# usb.net
KiCad netlist of a schematic drawn in EAGLE
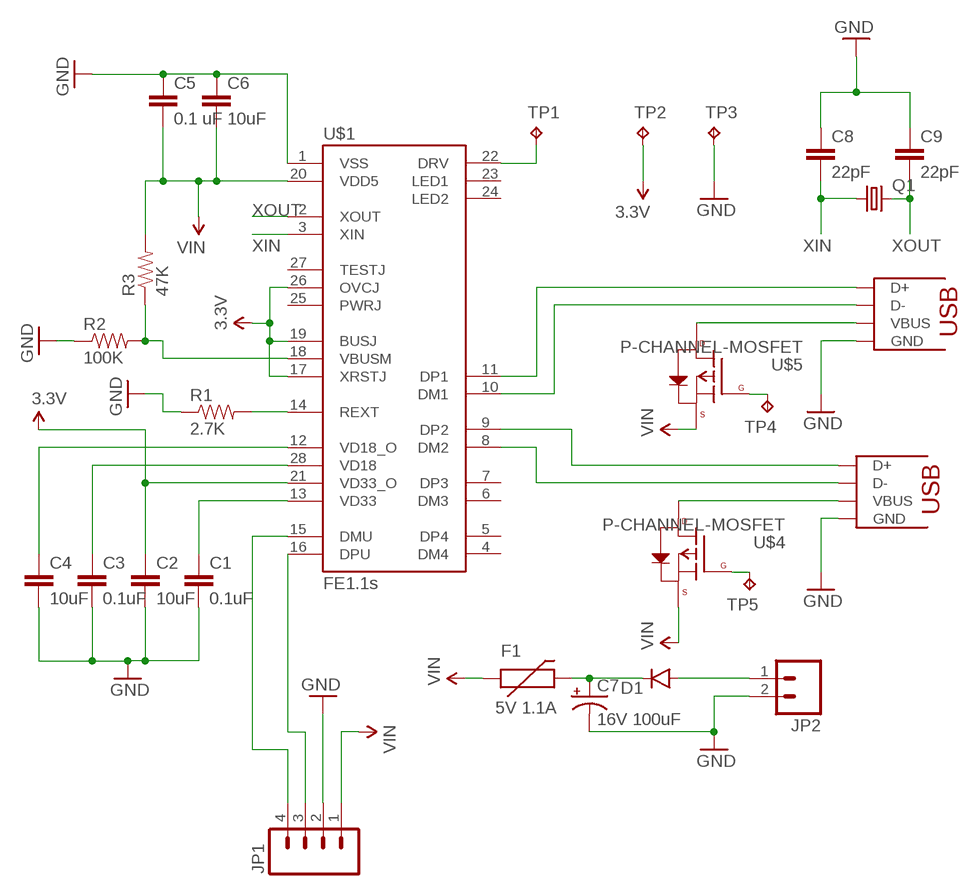
[diagram p0: schematic, sheet 1]

(export (version "E")
  (design (tool "Eeschema 10.0.6"))
  (components
    (comp (ref "C1")
      (value "0.1uF")
      (footprint "eagle-import:1206")
      (fields (field (name "MF") "TDK") (field (name "MPN") "CGA5L2C0G1H104J160AA"))
      (libsource (lib "eagle-import") (part "CAP1206"))
    )
    (comp (ref "C2")
      (value "10uF")
      (footprint "eagle-import:1206")
      (fields (field (name "MF") "TAIYO YUDEN") (field (name "MPN") "GMK316F106ZL-T"))
      (libsource (lib "eagle-import") (part "CAP1206"))
    )
    (comp (ref "C3")
      (value "0.1uF")
      (footprint "eagle-import:1206")
      (fields (field (name "MF") "TDK") (field (name "MPN") "CGA5L2C0G1H104J160AA"))
      (libsource (lib "eagle-import") (part "CAP1206"))
    )
    (comp (ref "C4")
      (value "10uF")
      (footprint "eagle-import:1206")
      (fields (field (name "MF") "TAIYO YUDEN") (field (name "MPN") "GMK316F106ZL-T"))
      (libsource (lib "eagle-import") (part "CAP1206"))
    )
    (comp (ref "C5")
      (value "0.1 uF")
      (footprint "eagle-import:1206")
      (fields (field (name "MF") "TDK") (field (name "MPN") "CGA5L2C0G1H104J160AA"))
      (libsource (lib "eagle-import") (part "CAP1206"))
    )
    (comp (ref "C6")
      (value "10uF")
      (footprint "eagle-import:1206")
      (fields (field (name "MF") "TAIYO YUDEN") (field (name "MPN") "GMK316F106ZL-T"))
      (libsource (lib "eagle-import") (part "CAP1206"))
    )
    (comp (ref "C7")
      (value "16V 100uF")
      (footprint "eagle-import:PANASONIC_D")
      (fields (field (name "MF") "PANASONIC ELECTRONIC COMPONENTS") (field (name "MPN") "EEEHA1C101WP"))
      (libsource (lib "eagle-import") (part "CAP_POLD"))
    )
    (comp (ref "C8")
      (value "22pF")
      (footprint "eagle-import:1206")
      (fields (field (name "MF") "AVX") (field (name "MPN") "12061A220JAT2A"))
      (libsource (lib "eagle-import") (part "CAP1206"))
    )
    (comp (ref "C9")
      (value "22pF")
      (footprint "eagle-import:1206")
      (fields (field (name "MF") "AVX") (field (name "MPN") "12061A220JAT2A"))
      (libsource (lib "eagle-import") (part "CAP1206"))
    )
    (comp (ref "D1")
      (value "DIODESMA")
      (footprint "eagle-import:SMA-DIODE")
      (fields (field (name "MF") "MULTICOMP") (field (name "MPN") "SMAJ5.0A"))
      (libsource (lib "eagle-import") (part "DIODESMA"))
    )
    (comp (ref "F1")
      (value "5V 1.1A")
      (footprint "eagle-import:PTC-1206")
      (libsource (lib "eagle-import") (part "PTCSMD"))
    )
    (comp (ref "JP1")
      (value "M04LONGPADS")
      (footprint "eagle-import:1X04_LONGPADS")
      (libsource (lib "eagle-import") (part "M04LONGPADS"))
    )
    (comp (ref "JP2")
      (value "M02PTH")
      (footprint "eagle-import:1X02")
      (libsource (lib "eagle-import") (part "M02PTH"))
    )
    (comp (ref "Q1")
      (value "CRYSTALCTS406")
      (footprint "eagle-import:CTS406")
      (fields
        (field (name "MF") "ABRACON")
        (field (name "MPN") "ABM3B-12.000MHZ-B2-T")
        (field (name "OC_FARNELL") "1611810")
      )
      (libsource (lib "eagle-import") (part "CRYSTALCTS406"))
    )
    (comp (ref "R1")
      (value "2.7K")
      (footprint "eagle-import:1206")
      (fields (field (name "MF") "WELWYN") (field (name "MPN") "WCR1206-2K7FI"))
      (libsource (lib "eagle-import") (part "RESISTOR1206"))
    )
    (comp (ref "R2")
      (value "100K")
      (footprint "eagle-import:1206")
      (fields (field (name "MF") "VISHAY") (field (name "MPN") "CRCW1206100KFKEA"))
      (libsource (lib "eagle-import") (part "RESISTOR1206"))
    )
    (comp (ref "R3")
      (value "47K")
      (footprint "eagle-import:1206")
      (fields (field (name "MF") "VISHAY") (field (name "MPN") "CRCW120647K0FKEA"))
      (libsource (lib "eagle-import") (part "RESISTOR1206"))
    )
    (comp (ref "TP1")
      (value "TP_DRV")
      (footprint "eagle-import:B2,54")
      (libsource (lib "eagle-import") (part "TPB2,54"))
    )
    (comp (ref "TP2")
      (value "TP_DRV")
      (footprint "eagle-import:B2,54")
      (libsource (lib "eagle-import") (part "TPB2,54"))
    )
    (comp (ref "TP3")
      (value "TP_DRV")
      (footprint "eagle-import:B2,54")
      (libsource (lib "eagle-import") (part "TPB2,54"))
    )
    (comp (ref "TP4")
      (value "TP_DRV")
      (footprint "eagle-import:B2,54")
      (libsource (lib "eagle-import") (part "TPB2,54"))
    )
    (comp (ref "TP5")
      (value "TP_DRV")
      (footprint "eagle-import:B2,54")
      (libsource (lib "eagle-import") (part "TPB2,54"))
    )
    (comp (ref "U$1")
      (value "FE1.1S")
      (footprint "eagle-import:FE1.1S_SSOP-28")
      (libsource (lib "eagle-import") (part "FE1.1S"))
    )
    (comp (ref "U$2")
      (value "USB-A-S")
      (footprint "eagle-import:USB-A-S-RA-PTH")
      (libsource (lib "eagle-import") (part "USB-A-S"))
    )
    (comp (ref "U$3")
      (value "USB-A-S")
      (footprint "eagle-import:USB-A-S-RA-PTH")
      (libsource (lib "eagle-import") (part "USB-A-S"))
    )
    (comp (ref "U$4")
      (value "P-CHANNEL-MOSFET")
      (footprint "eagle-import:SOT23-3")
      (fields (field (name "MF") "VISHAY") (field (name "MPN") "SI2301CDS-T1-E3"))
      (libsource (lib "eagle-import") (part "P-CHANNEL-MOSFET"))
    )
    (comp (ref "U$5")
      (value "P-CHANNEL-MOSFET")
      (footprint "eagle-import:SOT23-3")
      (fields (field (name "MF") "VISHAY") (field (name "MPN") "SI2301CDS-T1-E3"))
      (libsource (lib "eagle-import") (part "P-CHANNEL-MOSFET"))
    )
  )
  (nets
    (net (code "1") (name "/XIN") (class "Default")
      (node (ref "C8") (pin "2") (pinfunction "2_2") (pintype "passive"))
      (node (ref "Q1") (pin "1") (pinfunction "1_1") (pintype "passive"))
      (node (ref "U$1") (pin "3") (pinfunction "XIN_3") (pintype "bidirectional"))
    )
    (net (code "2") (name "/XOUT") (class "Default")
      (node (ref "C9") (pin "2") (pinfunction "2_2") (pintype "passive"))
      (node (ref "Q1") (pin "3") (pinfunction "2_3") (pintype "passive"))
      (node (ref "U$1") (pin "2") (pinfunction "XOUT_2") (pintype "bidirectional"))
    )
    (net (code "3") (name "3.3V") (class "Default")
      (node (ref "C2") (pin "1") (pinfunction "1_1") (pintype "passive"))
      (node (ref "TP2") (pin "TP") (pinfunction "TP_TP") (pintype "input"))
      (node (ref "U$1") (pin "17") (pinfunction "XRSTJ_17") (pintype "bidirectional"))
      (node (ref "U$1") (pin "19") (pinfunction "BUSJ_19") (pintype "bidirectional"))
      (node (ref "U$1") (pin "21") (pinfunction "VD33_O_21") (pintype "bidirectional"))
      (node (ref "U$1") (pin "26") (pinfunction "OVCJ_26") (pintype "bidirectional"))
    )
    (net (code "4") (name "GND") (class "Default")
      (node (ref "C1") (pin "2") (pinfunction "2_2") (pintype "passive"))
      (node (ref "C2") (pin "2") (pinfunction "2_2") (pintype "passive"))
      (node (ref "C3") (pin "2") (pinfunction "2_2") (pintype "passive"))
      (node (ref "C4") (pin "2") (pinfunction "2_2") (pintype "passive"))
      (node (ref "C5") (pin "1") (pinfunction "1_1") (pintype "passive"))
      (node (ref "C6") (pin "1") (pinfunction "1_1") (pintype "passive"))
      (node (ref "C7") (pin "-") (pinfunction "-_-") (pintype "passive"))
      (node (ref "C8") (pin "1") (pinfunction "1_1") (pintype "passive"))
      (node (ref "C9") (pin "1") (pinfunction "1_1") (pintype "passive"))
      (node (ref "JP1") (pin "2") (pinfunction "2_2") (pintype "passive"))
      (node (ref "JP2") (pin "2") (pinfunction "2_2") (pintype "passive"))
      (node (ref "R1") (pin "1") (pinfunction "1_1") (pintype "passive"))
      (node (ref "R2") (pin "1") (pinfunction "1_1") (pintype "passive"))
      (node (ref "TP3") (pin "TP") (pinfunction "TP_TP") (pintype "input"))
      (node (ref "U$1") (pin "1") (pinfunction "VSS_1") (pintype "bidirectional"))
      (node (ref "U$2") (pin "GND") (pinfunction "GND_GND") (pintype "bidirectional"))
      (node (ref "U$2") (pin "GND2") (pinfunction "GND_GND2") (pintype "bidirectional"))
      (node (ref "U$2") (pin "GND3") (pinfunction "GND_GND3") (pintype "bidirectional"))
      (node (ref "U$3") (pin "GND") (pinfunction "GND_GND") (pintype "bidirectional"))
      (node (ref "U$3") (pin "GND2") (pinfunction "GND_GND2") (pintype "bidirectional"))
      (node (ref "U$3") (pin "GND3") (pinfunction "GND_GND3") (pintype "bidirectional"))
    )
    (net (code "5") (name "Net-(C7-Pad+)") (class "Default")
      (node (ref "C7") (pin "+") (pinfunction "+_+") (pintype "passive"))
      (node (ref "D1") (pin "C") (pinfunction "C_C") (pintype "passive"))
      (node (ref "F1") (pin "2") (pinfunction "2_2") (pintype "bidirectional"))
    )
    (net (code "6") (name "Net-(D1-PadA)") (class "Default")
      (node (ref "D1") (pin "A") (pinfunction "A_A") (pintype "passive"))
      (node (ref "JP2") (pin "1") (pinfunction "1_1") (pintype "passive"))
    )
    (net (code "7") (name "Net-(U$1-DM1)") (class "Default")
      (node (ref "U$1") (pin "10") (pinfunction "DM1_10") (pintype "bidirectional"))
      (node (ref "U$2") (pin "D-") (pinfunction "D-_D-") (pintype "bidirectional"))
    )
    (net (code "8") (name "Net-(U$1-DM2)") (class "Default")
      (node (ref "U$1") (pin "8") (pinfunction "DM2_8") (pintype "bidirectional"))
      (node (ref "U$3") (pin "D-") (pinfunction "D-_D-") (pintype "bidirectional"))
    )
    (net (code "9") (name "Net-(U$1-DMU)") (class "Default")
      (node (ref "JP1") (pin "4") (pinfunction "4_4") (pintype "passive"))
      (node (ref "U$1") (pin "15") (pinfunction "DMU_15") (pintype "bidirectional"))
    )
    (net (code "10") (name "Net-(U$1-DP1)") (class "Default")
      (node (ref "U$1") (pin "11") (pinfunction "DP1_11") (pintype "bidirectional"))
      (node (ref "U$2") (pin "D+") (pinfunction "D+_D+") (pintype "bidirectional"))
    )
    (net (code "11") (name "Net-(U$1-DP2)") (class "Default")
      (node (ref "U$1") (pin "9") (pinfunction "DP2_9") (pintype "bidirectional"))
      (node (ref "U$3") (pin "D+") (pinfunction "D+_D+") (pintype "bidirectional"))
    )
    (net (code "12") (name "Net-(U$1-DPU)") (class "Default")
      (node (ref "JP1") (pin "3") (pinfunction "3_3") (pintype "passive"))
      (node (ref "U$1") (pin "16") (pinfunction "DPU_16") (pintype "bidirectional"))
    )
    (net (code "13") (name "Net-(U$1-DRV)") (class "Default")
      (node (ref "TP1") (pin "TP") (pinfunction "TP_TP") (pintype "input"))
      (node (ref "U$1") (pin "22") (pinfunction "DRV_22") (pintype "bidirectional"))
    )
    (net (code "14") (name "Net-(U$1-REXT)") (class "Default")
      (node (ref "R1") (pin "2") (pinfunction "2_2") (pintype "passive"))
      (node (ref "U$1") (pin "14") (pinfunction "REXT_14") (pintype "bidirectional"))
    )
    (net (code "15") (name "Net-(U$1-VBUSM)") (class "Default")
      (node (ref "R2") (pin "2") (pinfunction "2_2") (pintype "passive"))
      (node (ref "R3") (pin "1") (pinfunction "1_1") (pintype "passive"))
      (node (ref "U$1") (pin "18") (pinfunction "VBUSM_18") (pintype "bidirectional"))
    )
    (net (code "16") (name "Net-(U$1-VD18)") (class "Default")
      (node (ref "C3") (pin "1") (pinfunction "1_1") (pintype "passive"))
      (node (ref "U$1") (pin "28") (pinfunction "VD18_28") (pintype "bidirectional"))
    )
    (net (code "17") (name "Net-(U$1-VD18_O)") (class "Default")
      (node (ref "C4") (pin "1") (pinfunction "1_1") (pintype "passive"))
      (node (ref "U$1") (pin "12") (pinfunction "VD18_O_12") (pintype "bidirectional"))
    )
    (net (code "18") (name "Net-(U$1-VD33)") (class "Default")
      (node (ref "C1") (pin "1") (pinfunction "1_1") (pintype "passive"))
      (node (ref "U$1") (pin "13") (pinfunction "VD33_13") (pintype "bidirectional"))
    )
    (net (code "19") (name "Net-(U$4-D)") (class "Default")
      (node (ref "U$3") (pin "VBUS") (pinfunction "VBUS_VBUS") (pintype "bidirectional"))
      (node (ref "U$4") (pin "3") (pinfunction "D_3") (pintype "passive"))
    )
    (net (code "20") (name "Net-(U$4-G)") (class "Default")
      (node (ref "TP5") (pin "TP") (pinfunction "TP_TP") (pintype "input"))
      (node (ref "U$4") (pin "1") (pinfunction "G_1") (pintype "passive"))
    )
    (net (code "21") (name "Net-(U$5-D)") (class "Default")
      (node (ref "U$2") (pin "VBUS") (pinfunction "VBUS_VBUS") (pintype "bidirectional"))
      (node (ref "U$5") (pin "3") (pinfunction "D_3") (pintype "passive"))
    )
    (net (code "22") (name "Net-(U$5-G)") (class "Default")
      (node (ref "TP4") (pin "TP") (pinfunction "TP_TP") (pintype "input"))
      (node (ref "U$5") (pin "1") (pinfunction "G_1") (pintype "passive"))
    )
    (net (code "23") (name "VIN") (class "Default")
      (node (ref "C5") (pin "2") (pinfunction "2_2") (pintype "passive"))
      (node (ref "C6") (pin "2") (pinfunction "2_2") (pintype "passive"))
      (node (ref "F1") (pin "1") (pinfunction "1_1") (pintype "bidirectional"))
      (node (ref "JP1") (pin "1") (pinfunction "1_1") (pintype "passive"))
      (node (ref "R3") (pin "2") (pinfunction "2_2") (pintype "passive"))
      (node (ref "U$1") (pin "20") (pinfunction "VDD5_20") (pintype "bidirectional"))
      (node (ref "U$4") (pin "2") (pinfunction "S_2") (pintype "passive"))
      (node (ref "U$5") (pin "2") (pinfunction "S_2") (pintype "passive"))
    )
    (net (code "24") (name "unconnected-(U$1-DM3-Pad6)") (class "Default")
      (node (ref "U$1") (pin "6") (pinfunction "DM3_6") (pintype "bidirectional"))
    )
    (net (code "25") (name "unconnected-(U$1-DM4-Pad4)") (class "Default")
      (node (ref "U$1") (pin "4") (pinfunction "DM4_4") (pintype "bidirectional"))
    )
    (net (code "26") (name "unconnected-(U$1-DP3-Pad7)") (class "Default")
      (node (ref "U$1") (pin "7") (pinfunction "DP3_7") (pintype "bidirectional"))
    )
    (net (code "27") (name "unconnected-(U$1-DP4-Pad5)") (class "Default")
      (node (ref "U$1") (pin "5") (pinfunction "DP4_5") (pintype "bidirectional"))
    )
    (net (code "28") (name "unconnected-(U$1-LED1-Pad23)") (class "Default")
      (node (ref "U$1") (pin "23") (pinfunction "LED1_23") (pintype "bidirectional"))
    )
    (net (code "29") (name "unconnected-(U$1-LED2-Pad24)") (class "Default")
      (node (ref "U$1") (pin "24") (pinfunction "LED2_24") (pintype "bidirectional"))
    )
    (net (code "30") (name "unconnected-(U$1-PWRJ-Pad25)") (class "Default")
      (node (ref "U$1") (pin "25") (pinfunction "PWRJ_25") (pintype "bidirectional"))
    )
    (net (code "31") (name "unconnected-(U$1-TESTJ-Pad27)") (class "Default")
      (node (ref "U$1") (pin "27") (pinfunction "TESTJ_27") (pintype "bidirectional"))
    )
  )
)
